# Pocket_Simon_Schematic.net
KiCad netlist of a schematic drawn in EasyEDA
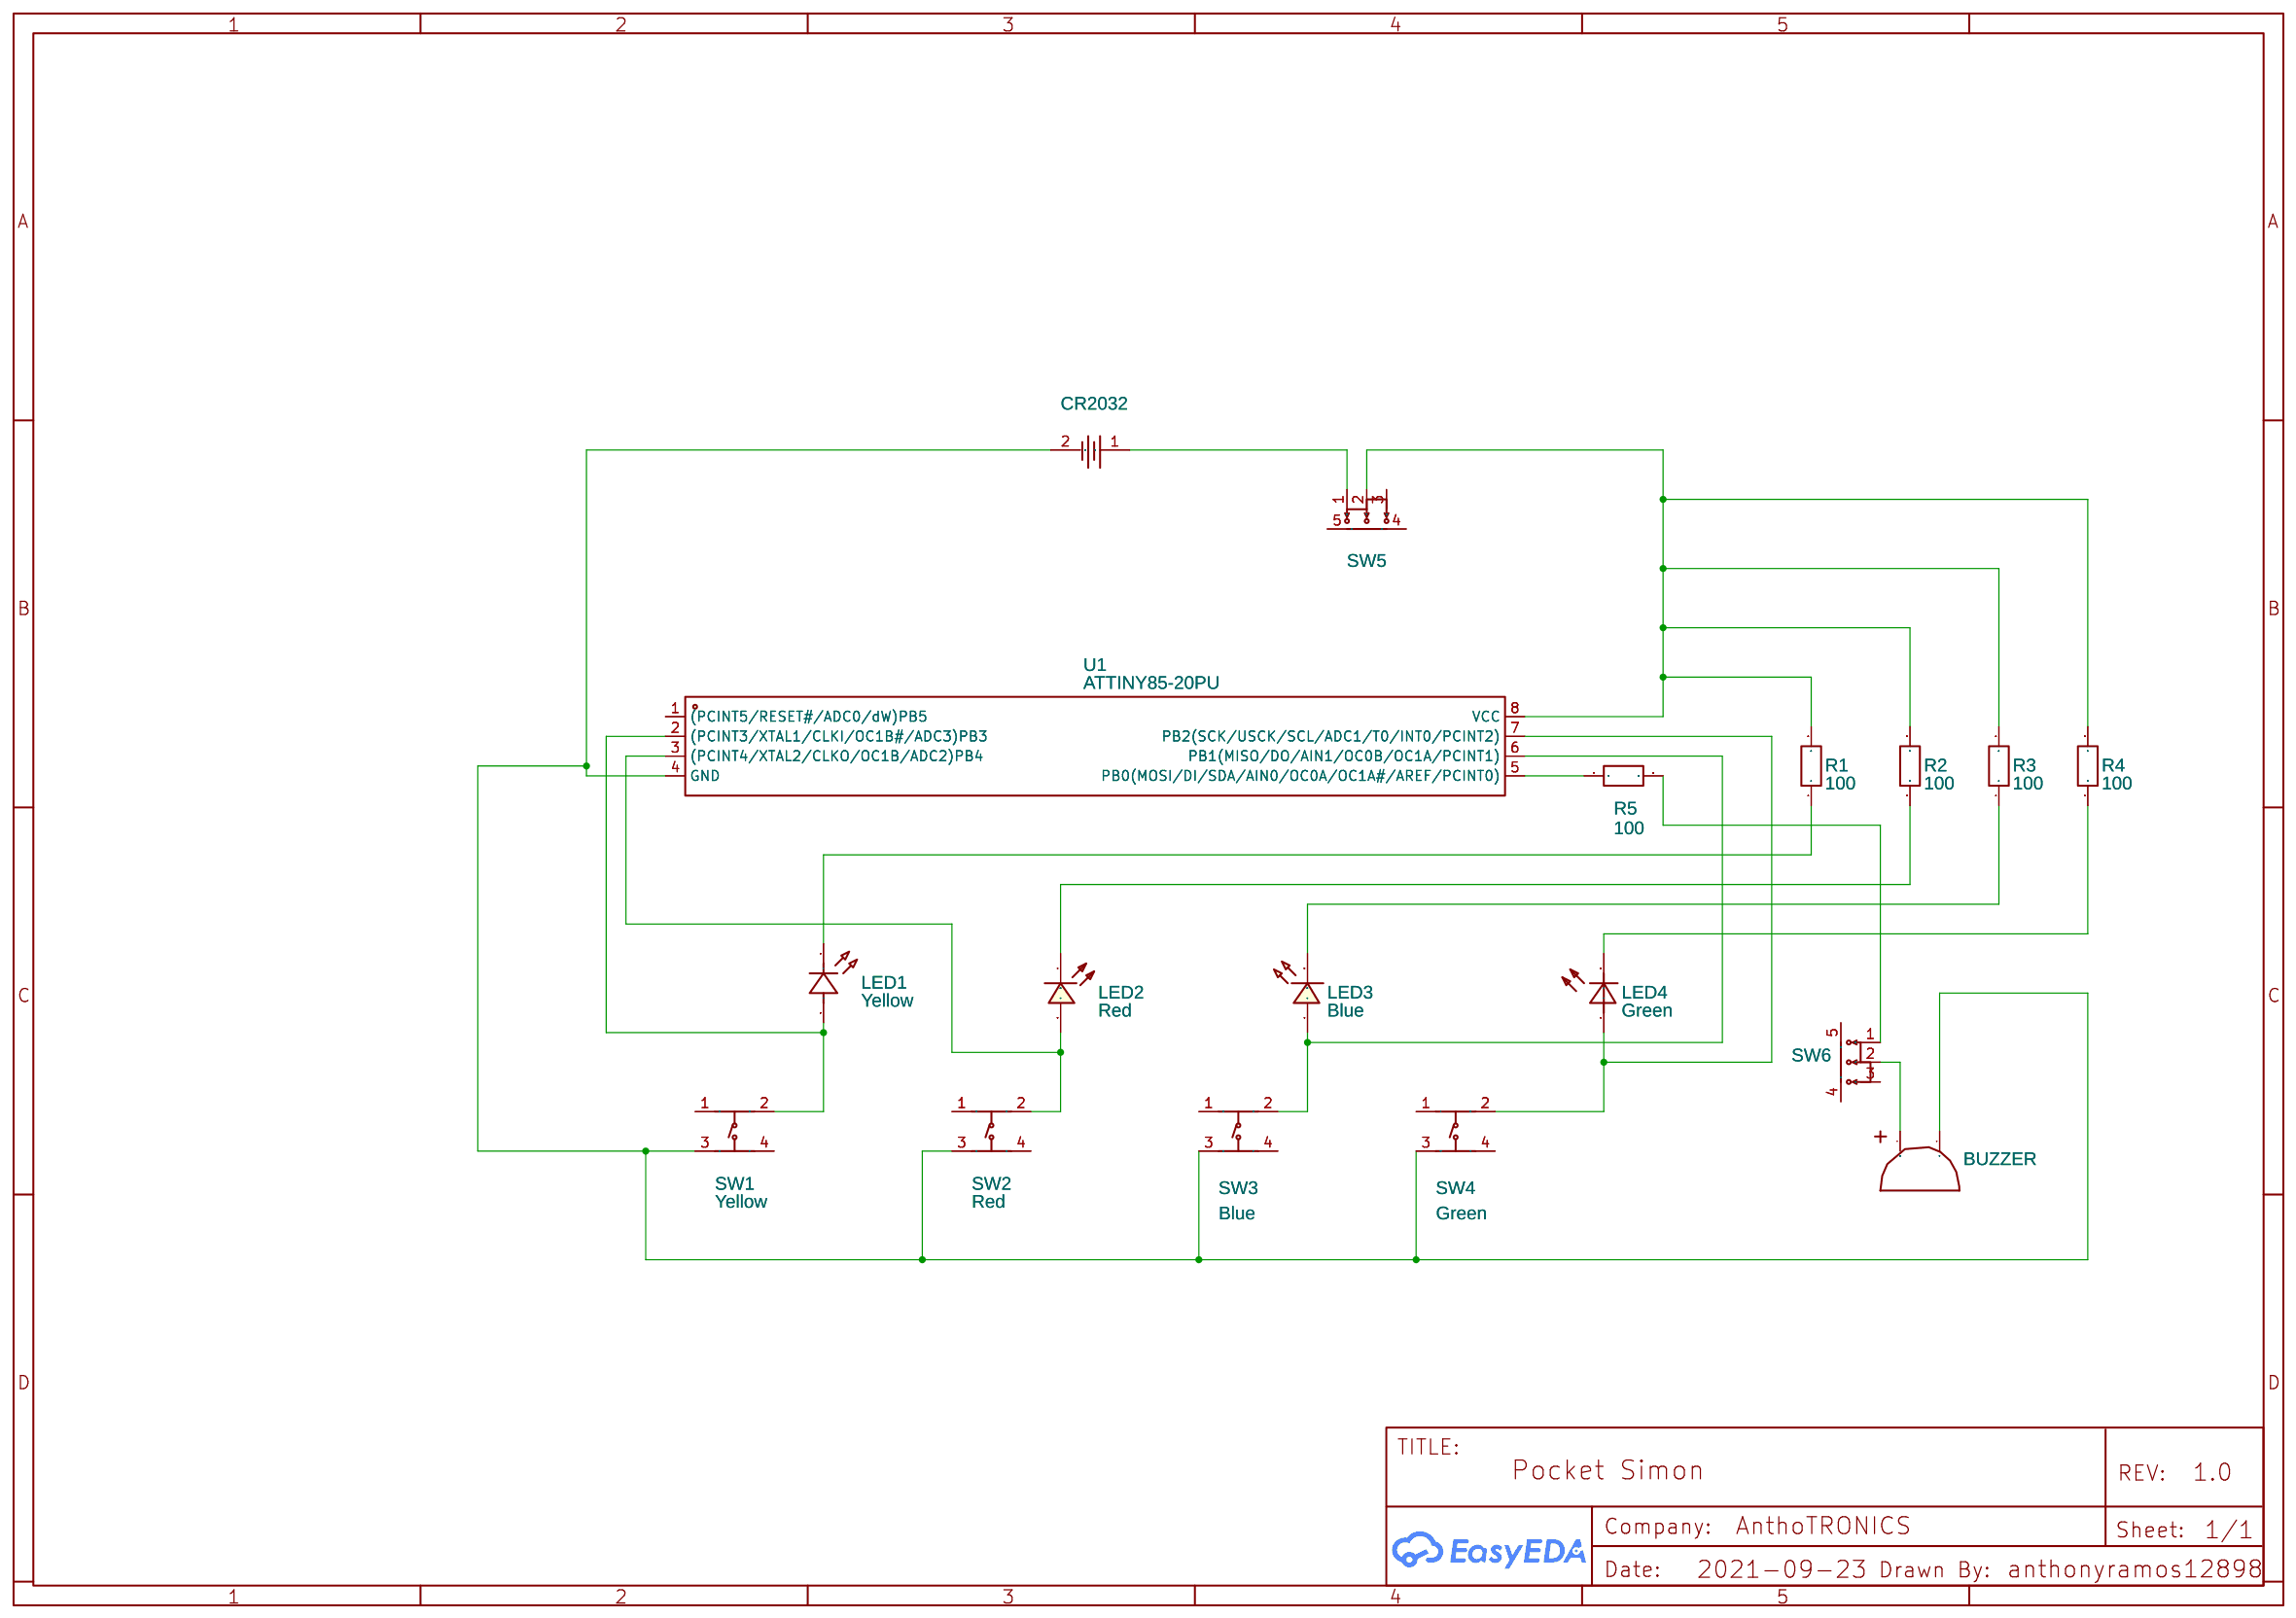
[diagram p0: schematic sheet]

(export (version "E")
  (design (tool "Eeschema 10.0.6"))
  (components
    (comp (ref "BUZZER") (value "BUZZER") (libsource (lib "") (part "BUZZER")))
    (comp (ref "CR2032")
      (value "BS-23-A1AK001")
      (fields (field (name "BOM_Supplier Part") "C964803"))
      (libsource (lib "") (part "BS-23-A1AK001"))
    )
    (comp (ref "LED1")
      (value "Yellow")
      (fields
        (field (name "BOM_Manufacturer Part") "TZ-L2-05YYBY1YCJ30-001")
        (field (name "BOM_Supplier Part") "C779441")
      )
      (libsource (lib "") (part "TZ-L2-05YYBY1YCJ30-001"))
    )
    (comp (ref "LED2")
      (value "Red")
      (fields
        (field (name "BOM_Manufacturer Part") "333-2SDRD/S530-A3-L")
        (field (name "BOM_Supplier Part") "C409526")
      )
      (libsource (lib "") (part "333-2SDRD/S530-A3-L"))
    )
    (comp (ref "LED3") (value "Blue") (libsource (lib "") (part "LED-TH-5mm_W")))
    (comp (ref "LED4") (value "Green") (libsource (lib "") (part "LED AL307 Green")))
    (comp (ref "R1")
      (value "100")
      (fields
        (field (name "BOM_Manufacturer Part") "MFR0W4F150KA50")
        (field (name "BOM_Supplier Part") "C66716")
      )
      (libsource (lib "") (part "MFR0W4F150KA50_C66716"))
    )
    (comp (ref "R2")
      (value "100")
      (fields
        (field (name "BOM_Manufacturer Part") "MFR0W4F150KA50")
        (field (name "BOM_Supplier Part") "C66716")
      )
      (libsource (lib "") (part "MFR0W4F150KA50_C66716"))
    )
    (comp (ref "R3")
      (value "100")
      (fields
        (field (name "BOM_Manufacturer Part") "MFR0W4F150KA50")
        (field (name "BOM_Supplier Part") "C66716")
      )
      (libsource (lib "") (part "MFR0W4F150KA50_C66716"))
    )
    (comp (ref "R4")
      (value "100")
      (fields
        (field (name "BOM_Manufacturer Part") "MFR0W4F150KA50")
        (field (name "BOM_Supplier Part") "C66716")
      )
      (libsource (lib "") (part "MFR0W4F150KA50_C66716"))
    )
    (comp (ref "R5")
      (value "100")
      (fields
        (field (name "BOM_Manufacturer Part") "MFR0W4F150KA50")
        (field (name "BOM_Supplier Part") "C66716")
      )
      (libsource (lib "") (part "MFR0W4F150KA50_C66716_1"))
    )
    (comp (ref "SW1")
      (value "Yellow")
      (fields
        (field (name "BOM_Manufacturer Part") "TS-KG1103-BB65F")
        (field (name "BOM_Supplier Part") "C2874457")
      )
      (libsource (lib "") (part "TS-KG1103-BB65F"))
    )
    (comp (ref "SW2")
      (value "Red")
      (fields
        (field (name "BOM_Manufacturer Part") "TS-KG1103-BB65F")
        (field (name "BOM_Supplier Part") "C2874457")
      )
      (libsource (lib "") (part "TS-KG1103-BB65F"))
    )
    (comp (ref "SW3")
      (value "Blue")
      (fields
        (field (name "BOM_Manufacturer Part") "TS-KG1103-BB65F")
        (field (name "BOM_Supplier Part") "C2874457")
      )
      (libsource (lib "") (part "TS-KG1103-BB65F"))
    )
    (comp (ref "SW4")
      (value "Green")
      (fields
        (field (name "BOM_Manufacturer Part") "TS-KG1103-BB65F")
        (field (name "BOM_Supplier Part") "C2874457")
      )
      (libsource (lib "") (part "TS-KG1103-BB65F"))
    )
    (comp (ref "SW5")
      (value "SS-12D02-G3")
      (fields (field (name "BOM_Supplier Part") "C521447"))
      (libsource (lib "") (part "SS-12D02-G3_1"))
    )
    (comp (ref "SW6")
      (value "SS-12D02-G3")
      (fields (field (name "BOM_Supplier Part") "C521447"))
      (libsource (lib "") (part "SS-12D02-G3"))
    )
    (comp (ref "U1")
      (value "ATTINY85-20PU")
      (fields (field (name "BOM_Supplier Part") "C965497"))
      (libsource (lib "") (part "ATTINY85-20PU"))
    )
  )
  (nets
    (net (code "1") (name "Net-(BUZZER-1)") (class "Default")
      (node (ref "BUZZER") (pin "+") (pinfunction "1_+") (pintype "unspecified"))
      (node (ref "CR2032") (pin "2") (pinfunction "2_2") (pintype "input"))
      (node (ref "SW1") (pin "3") (pinfunction "3_3") (pintype "unspecified"))
      (node (ref "SW2") (pin "3") (pinfunction "3_3") (pintype "unspecified"))
      (node (ref "SW3") (pin "3") (pinfunction "3_3") (pintype "unspecified"))
      (node (ref "SW4") (pin "3") (pinfunction "3_3") (pintype "unspecified"))
      (node (ref "U1") (pin "4") (pinfunction "GND_4") (pintype "unspecified"))
    )
    (net (code "2") (name "Net-(BUZZER-2)") (class "Default")
      (node (ref "BUZZER") (pin "-") (pinfunction "2_-") (pintype "unspecified"))
      (node (ref "SW6") (pin "2") (pinfunction "2_2") (pintype "unspecified"))
    )
    (net (code "3") (name "Net-(CR2032-Pad1)") (class "Default")
      (node (ref "CR2032") (pin "1") (pinfunction "1_1") (pintype "input"))
      (node (ref "SW5") (pin "1") (pinfunction "1_1") (pintype "unspecified"))
    )
    (net (code "4") (name "Net-(LED1-+)") (class "Default")
      (node (ref "LED1") (pin "2") (pinfunction "+_2") (pintype "unspecified"))
      (node (ref "SW1") (pin "2") (pinfunction "2_2") (pintype "unspecified"))
      (node (ref "U1") (pin "2") (pinfunction "(PCINT3/XTAL1/CLKI/OC1B#/ADC3)PB3_2") (pintype "unspecified"))
    )
    (net (code "5") (name "Net-(LED1--)") (class "Default")
      (node (ref "LED1") (pin "1") (pinfunction "-_1") (pintype "unspecified"))
      (node (ref "R1") (pin "1") (pinfunction "1_1") (pintype "unspecified"))
    )
    (net (code "6") (name "Net-(LED2-A)") (class "Default")
      (node (ref "LED2") (pin "2") (pinfunction "A_2") (pintype "unspecified"))
      (node (ref "SW2") (pin "2") (pinfunction "2_2") (pintype "unspecified"))
      (node (ref "U1") (pin "3") (pinfunction "(PCINT4/XTAL2/CLKO/OC1B/ADC2)PB4_3") (pintype "unspecified"))
    )
    (net (code "7") (name "Net-(LED2-C)") (class "Default")
      (node (ref "LED2") (pin "1") (pinfunction "C_1") (pintype "unspecified"))
      (node (ref "R2") (pin "1") (pinfunction "1_1") (pintype "unspecified"))
    )
    (net (code "8") (name "Net-(LED3-Pad2)") (class "Default")
      (node (ref "LED3") (pin "2") (pinfunction "2_2") (pintype "unspecified"))
      (node (ref "R3") (pin "1") (pinfunction "1_1") (pintype "unspecified"))
    )
    (net (code "9") (name "Net-(LED4-+)") (class "Default")
      (node (ref "LED4") (pin "1") (pinfunction "+_1") (pintype "unspecified"))
      (node (ref "SW4") (pin "2") (pinfunction "2_2") (pintype "unspecified"))
      (node (ref "U1") (pin "7") (pinfunction "PB2(SCK/USCK/SCL/ADC1/T0/INT0/PCINT2)_7") (pintype "unspecified"))
    )
    (net (code "10") (name "Net-(LED4--)") (class "Default")
      (node (ref "LED4") (pin "2") (pinfunction "-_2") (pintype "unspecified"))
      (node (ref "R4") (pin "1") (pinfunction "1_1") (pintype "unspecified"))
    )
    (net (code "11") (name "Net-(R5-Pad2)") (class "Default")
      (node (ref "R5") (pin "2") (pinfunction "2_2") (pintype "unspecified"))
      (node (ref "SW6") (pin "1") (pinfunction "1_1") (pintype "unspecified"))
    )
    (net (code "12") (name "Net-(U1-PB0(MOSI{slash}DI{slash}SDA{slash}AIN0{slash}OC0A{slash}OC1A#{slash}AREF{slash}PCINT0))") (class "Default")
      (node (ref "R5") (pin "1") (pinfunction "1_1") (pintype "unspecified"))
      (node (ref "U1") (pin "5") (pinfunction "PB0(MOSI/DI/SDA/AIN0/OC0A/OC1A#/AREF/PCINT0)_5") (pintype "unspecified"))
    )
    (net (code "13") (name "Net-(U1-PB1(MISO{slash}DO{slash}AIN1{slash}OC0B{slash}OC1A{slash}PCINT1))") (class "Default")
      (node (ref "LED3") (pin "1") (pinfunction "1_1") (pintype "unspecified"))
      (node (ref "SW3") (pin "2") (pinfunction "2_2") (pintype "unspecified"))
      (node (ref "U1") (pin "6") (pinfunction "PB1(MISO/DO/AIN1/OC0B/OC1A/PCINT1)_6") (pintype "unspecified"))
    )
    (net (code "14") (name "Net-(U1-VCC)") (class "Default")
      (node (ref "R1") (pin "2") (pinfunction "2_2") (pintype "unspecified"))
      (node (ref "R2") (pin "2") (pinfunction "2_2") (pintype "unspecified"))
      (node (ref "R3") (pin "2") (pinfunction "2_2") (pintype "unspecified"))
      (node (ref "R4") (pin "2") (pinfunction "2_2") (pintype "unspecified"))
      (node (ref "SW5") (pin "2") (pinfunction "2_2") (pintype "unspecified"))
      (node (ref "U1") (pin "8") (pinfunction "VCC_8") (pintype "unspecified"))
    )
    (net (code "15") (name "unconnected-(SW1-Pad1)") (class "Default")
      (node (ref "SW1") (pin "1") (pinfunction "1_1") (pintype "unspecified"))
    )
    (net (code "16") (name "unconnected-(SW1-Pad4)") (class "Default")
      (node (ref "SW1") (pin "4") (pinfunction "4_4") (pintype "unspecified"))
    )
    (net (code "17") (name "unconnected-(SW2-Pad1)") (class "Default")
      (node (ref "SW2") (pin "1") (pinfunction "1_1") (pintype "unspecified"))
    )
    (net (code "18") (name "unconnected-(SW2-Pad4)") (class "Default")
      (node (ref "SW2") (pin "4") (pinfunction "4_4") (pintype "unspecified"))
    )
    (net (code "19") (name "unconnected-(SW3-Pad1)") (class "Default")
      (node (ref "SW3") (pin "1") (pinfunction "1_1") (pintype "unspecified"))
    )
    (net (code "20") (name "unconnected-(SW3-Pad4)") (class "Default")
      (node (ref "SW3") (pin "4") (pinfunction "4_4") (pintype "unspecified"))
    )
    (net (code "21") (name "unconnected-(SW4-Pad1)") (class "Default")
      (node (ref "SW4") (pin "1") (pinfunction "1_1") (pintype "unspecified"))
    )
    (net (code "22") (name "unconnected-(SW4-Pad4)") (class "Default")
      (node (ref "SW4") (pin "4") (pinfunction "4_4") (pintype "unspecified"))
    )
    (net (code "23") (name "unconnected-(SW5-Pad3)") (class "Default")
      (node (ref "SW5") (pin "3") (pinfunction "3_3") (pintype "unspecified"))
    )
    (net (code "24") (name "unconnected-(SW5-Pad4)") (class "Default")
      (node (ref "SW5") (pin "4") (pinfunction "4_4") (pintype "unspecified"))
    )
    (net (code "25") (name "unconnected-(SW5-Pad5)") (class "Default")
      (node (ref "SW5") (pin "5") (pinfunction "5_5") (pintype "unspecified"))
    )
    (net (code "26") (name "unconnected-(SW6-Pad3)") (class "Default")
      (node (ref "SW6") (pin "3") (pinfunction "3_3") (pintype "unspecified"))
    )
    (net (code "27") (name "unconnected-(SW6-Pad4)") (class "Default")
      (node (ref "SW6") (pin "4") (pinfunction "4_4") (pintype "unspecified"))
    )
    (net (code "28") (name "unconnected-(SW6-Pad5)") (class "Default")
      (node (ref "SW6") (pin "5") (pinfunction "5_5") (pintype "unspecified"))
    )
    (net (code "29") (name "unconnected-(U1-(PCINT5{slash}RESET#{slash}ADC0{slash}dW)PB5-Pad1)") (class "Default")
      (node (ref "U1") (pin "1") (pinfunction "(PCINT5/RESET#/ADC0/dW)PB5_1") (pintype "unspecified"))
    )
  )
)
